# oresat0-plusz-end-card.net
KiCad netlist of a schematic drawn in EAGLE
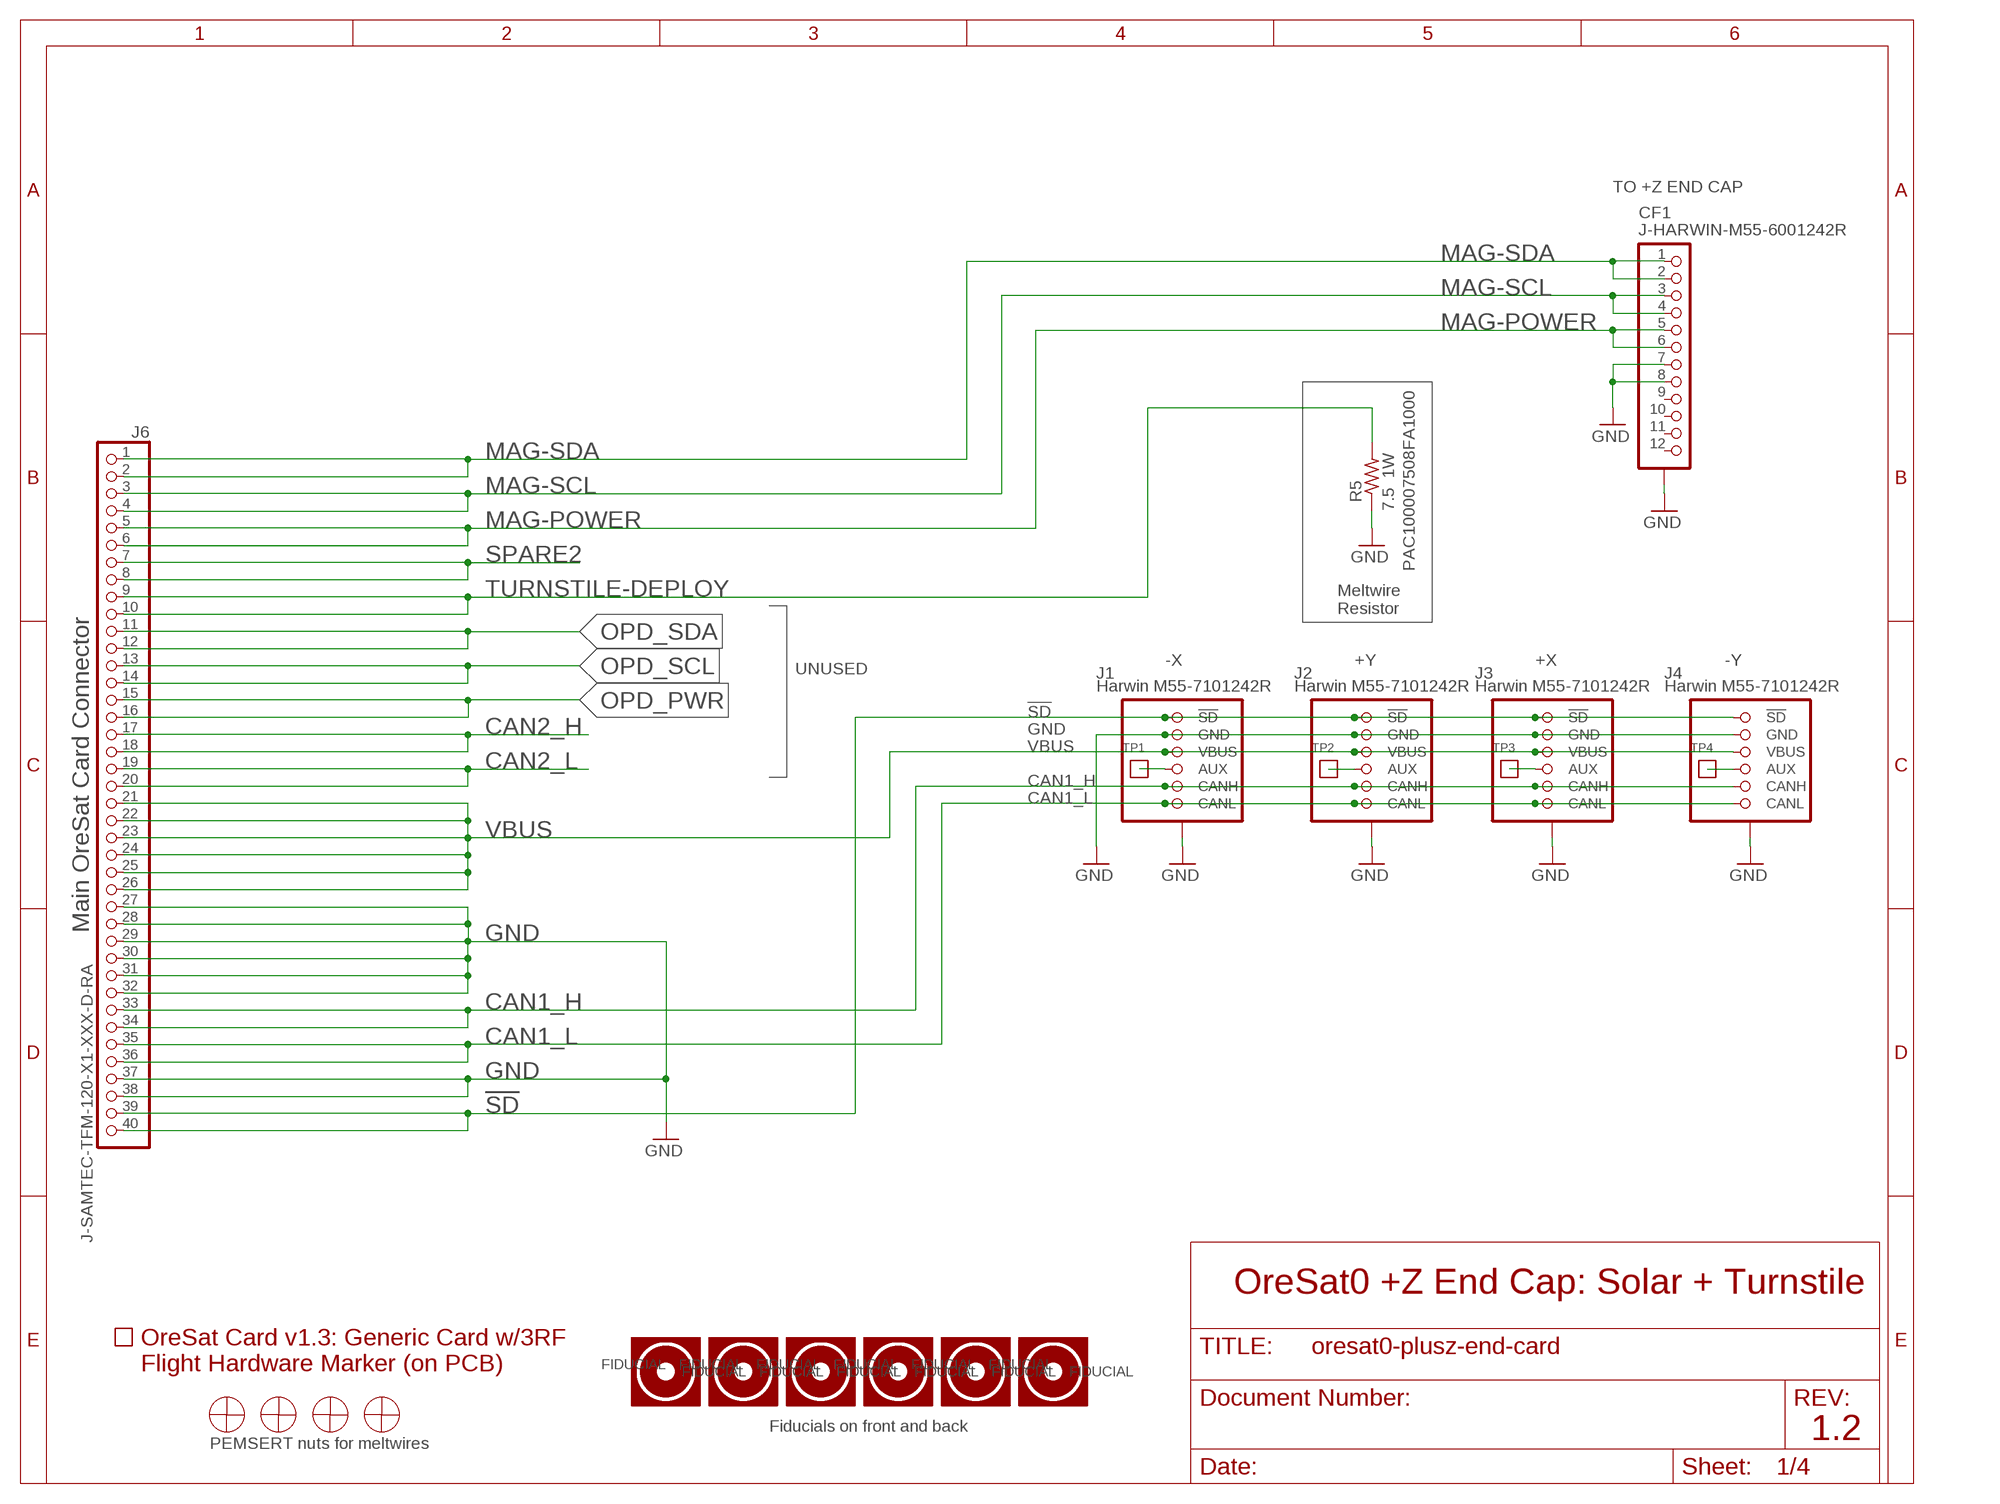
[diagram p0: schematic, sheet 1]
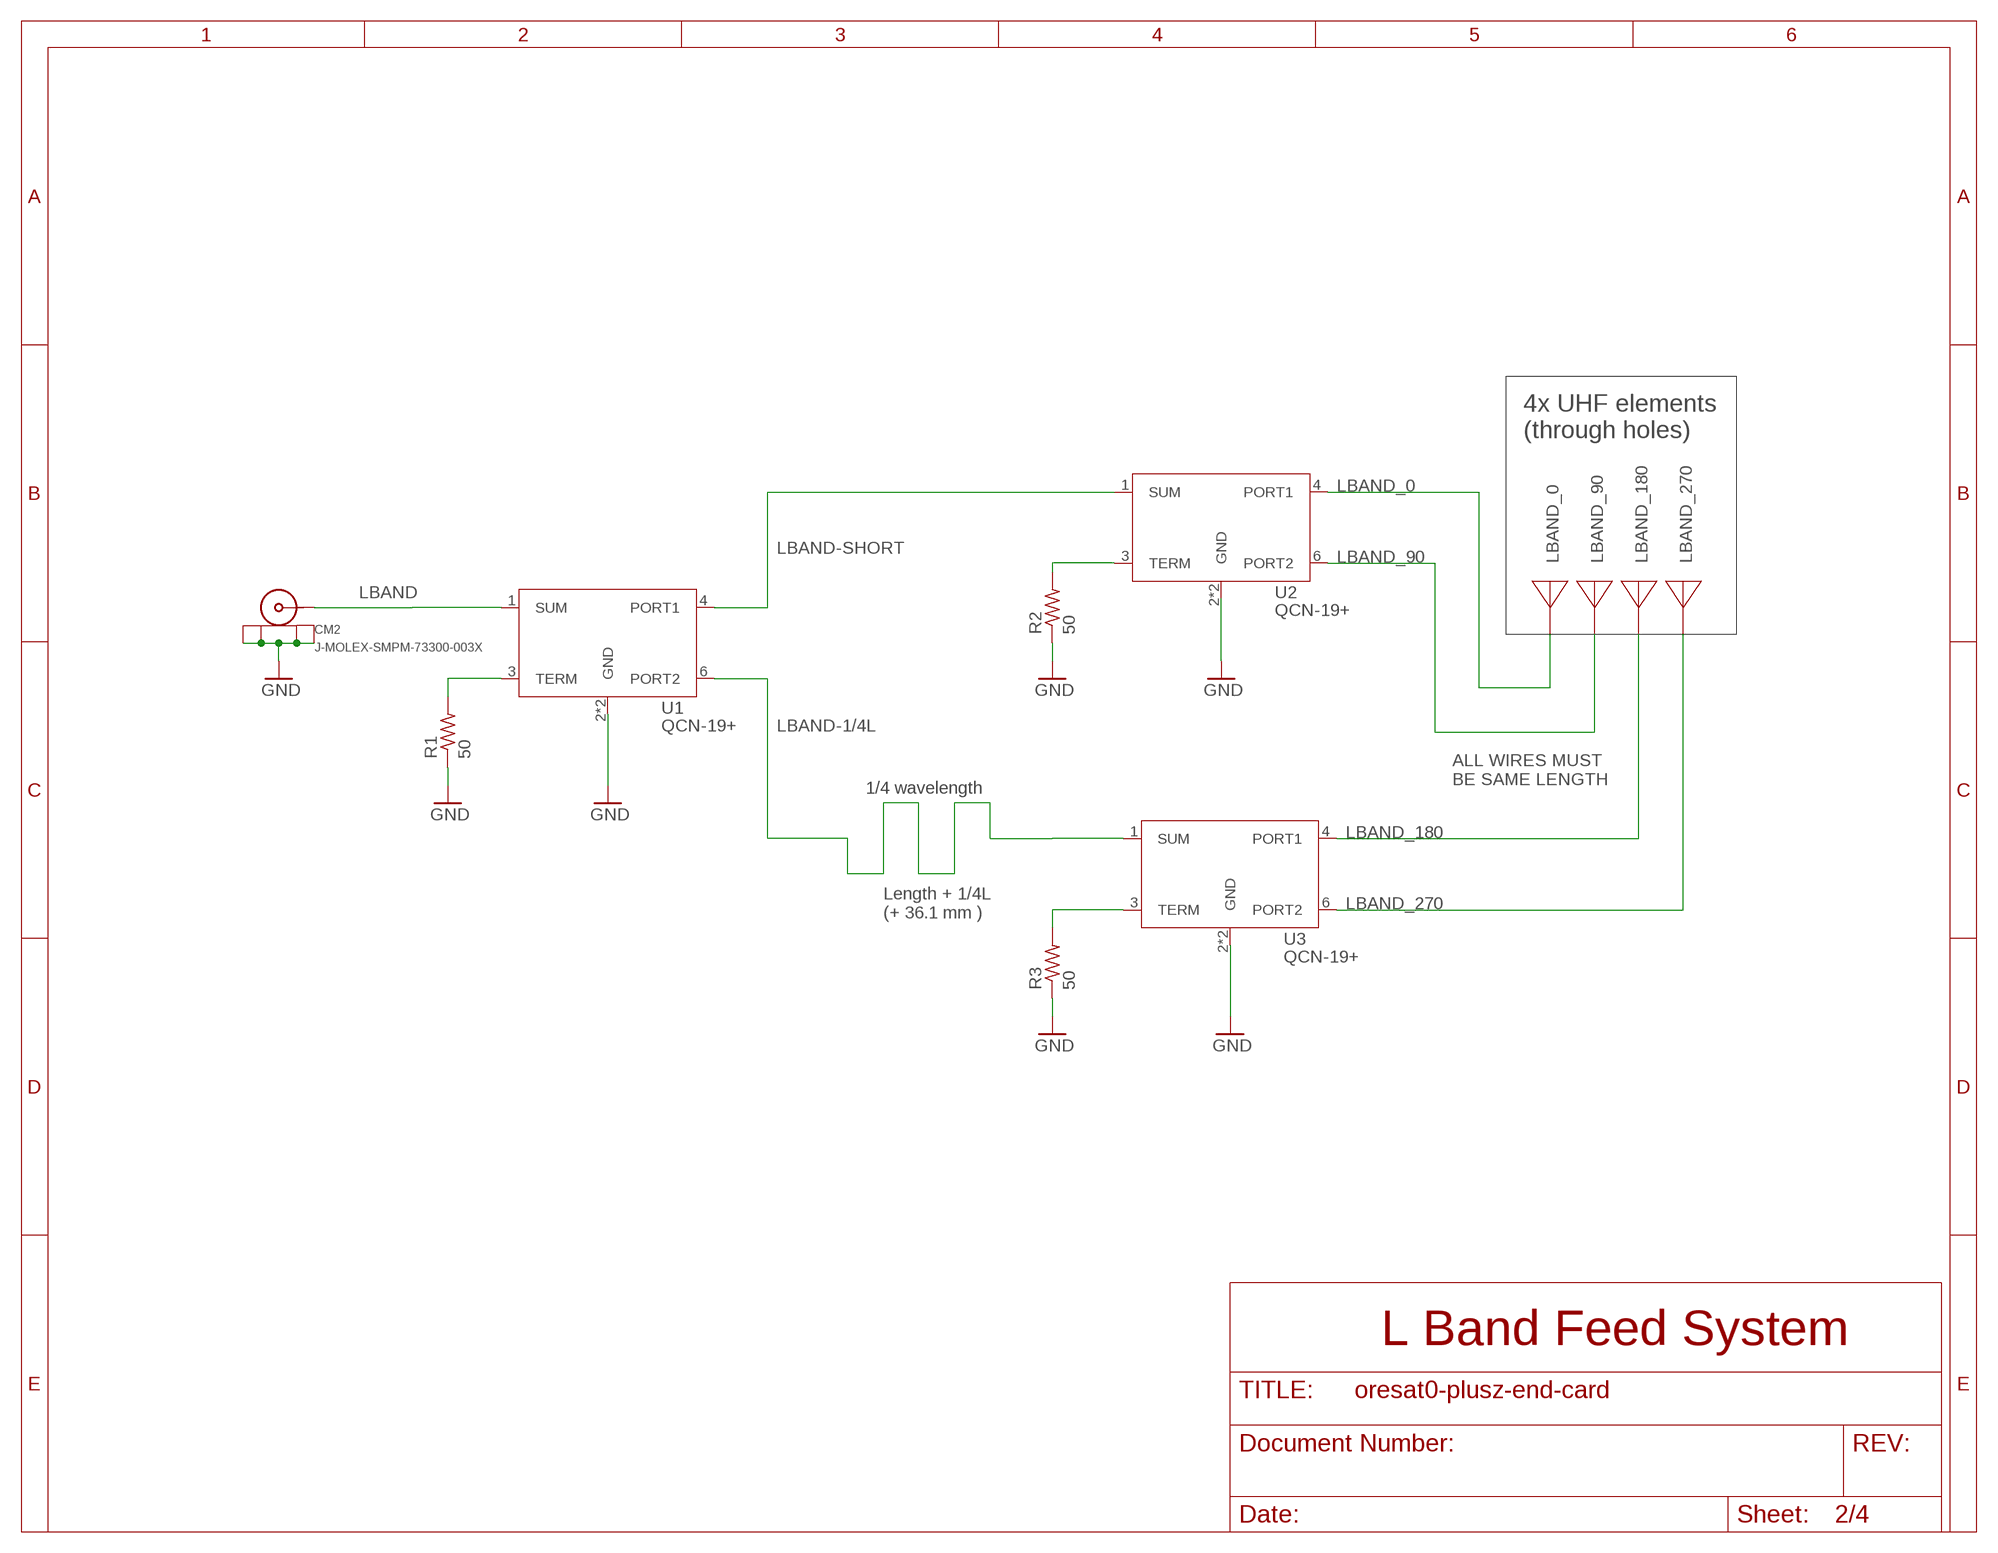
[diagram p1: schematic, sheet 2]
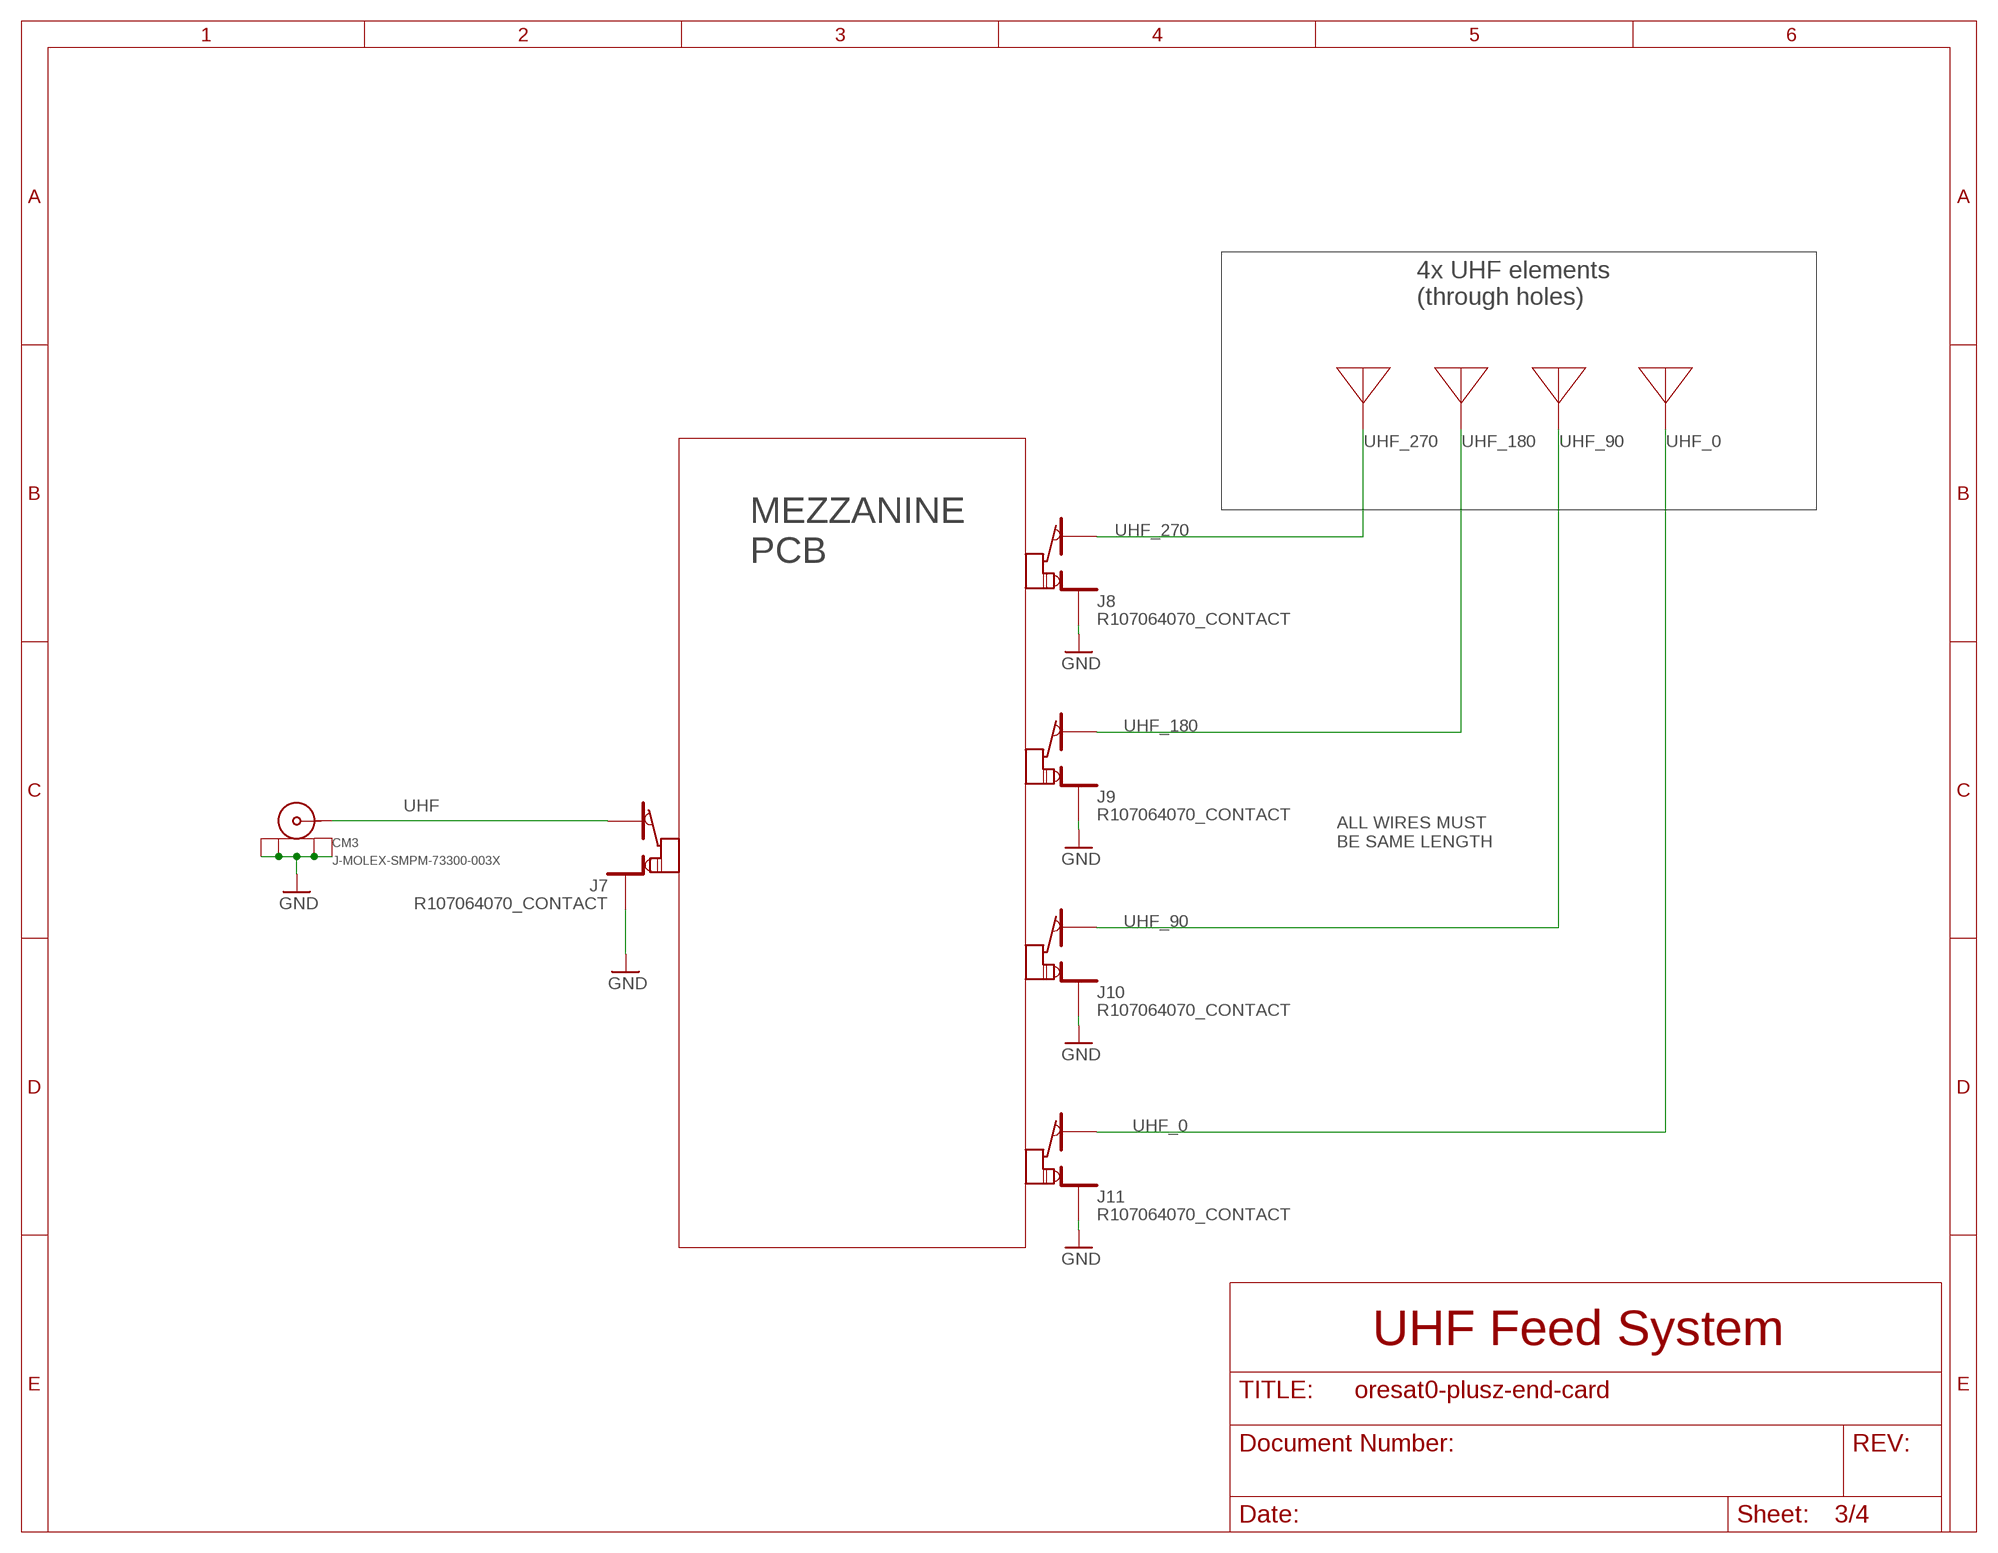
[diagram p2: schematic, sheet 3]
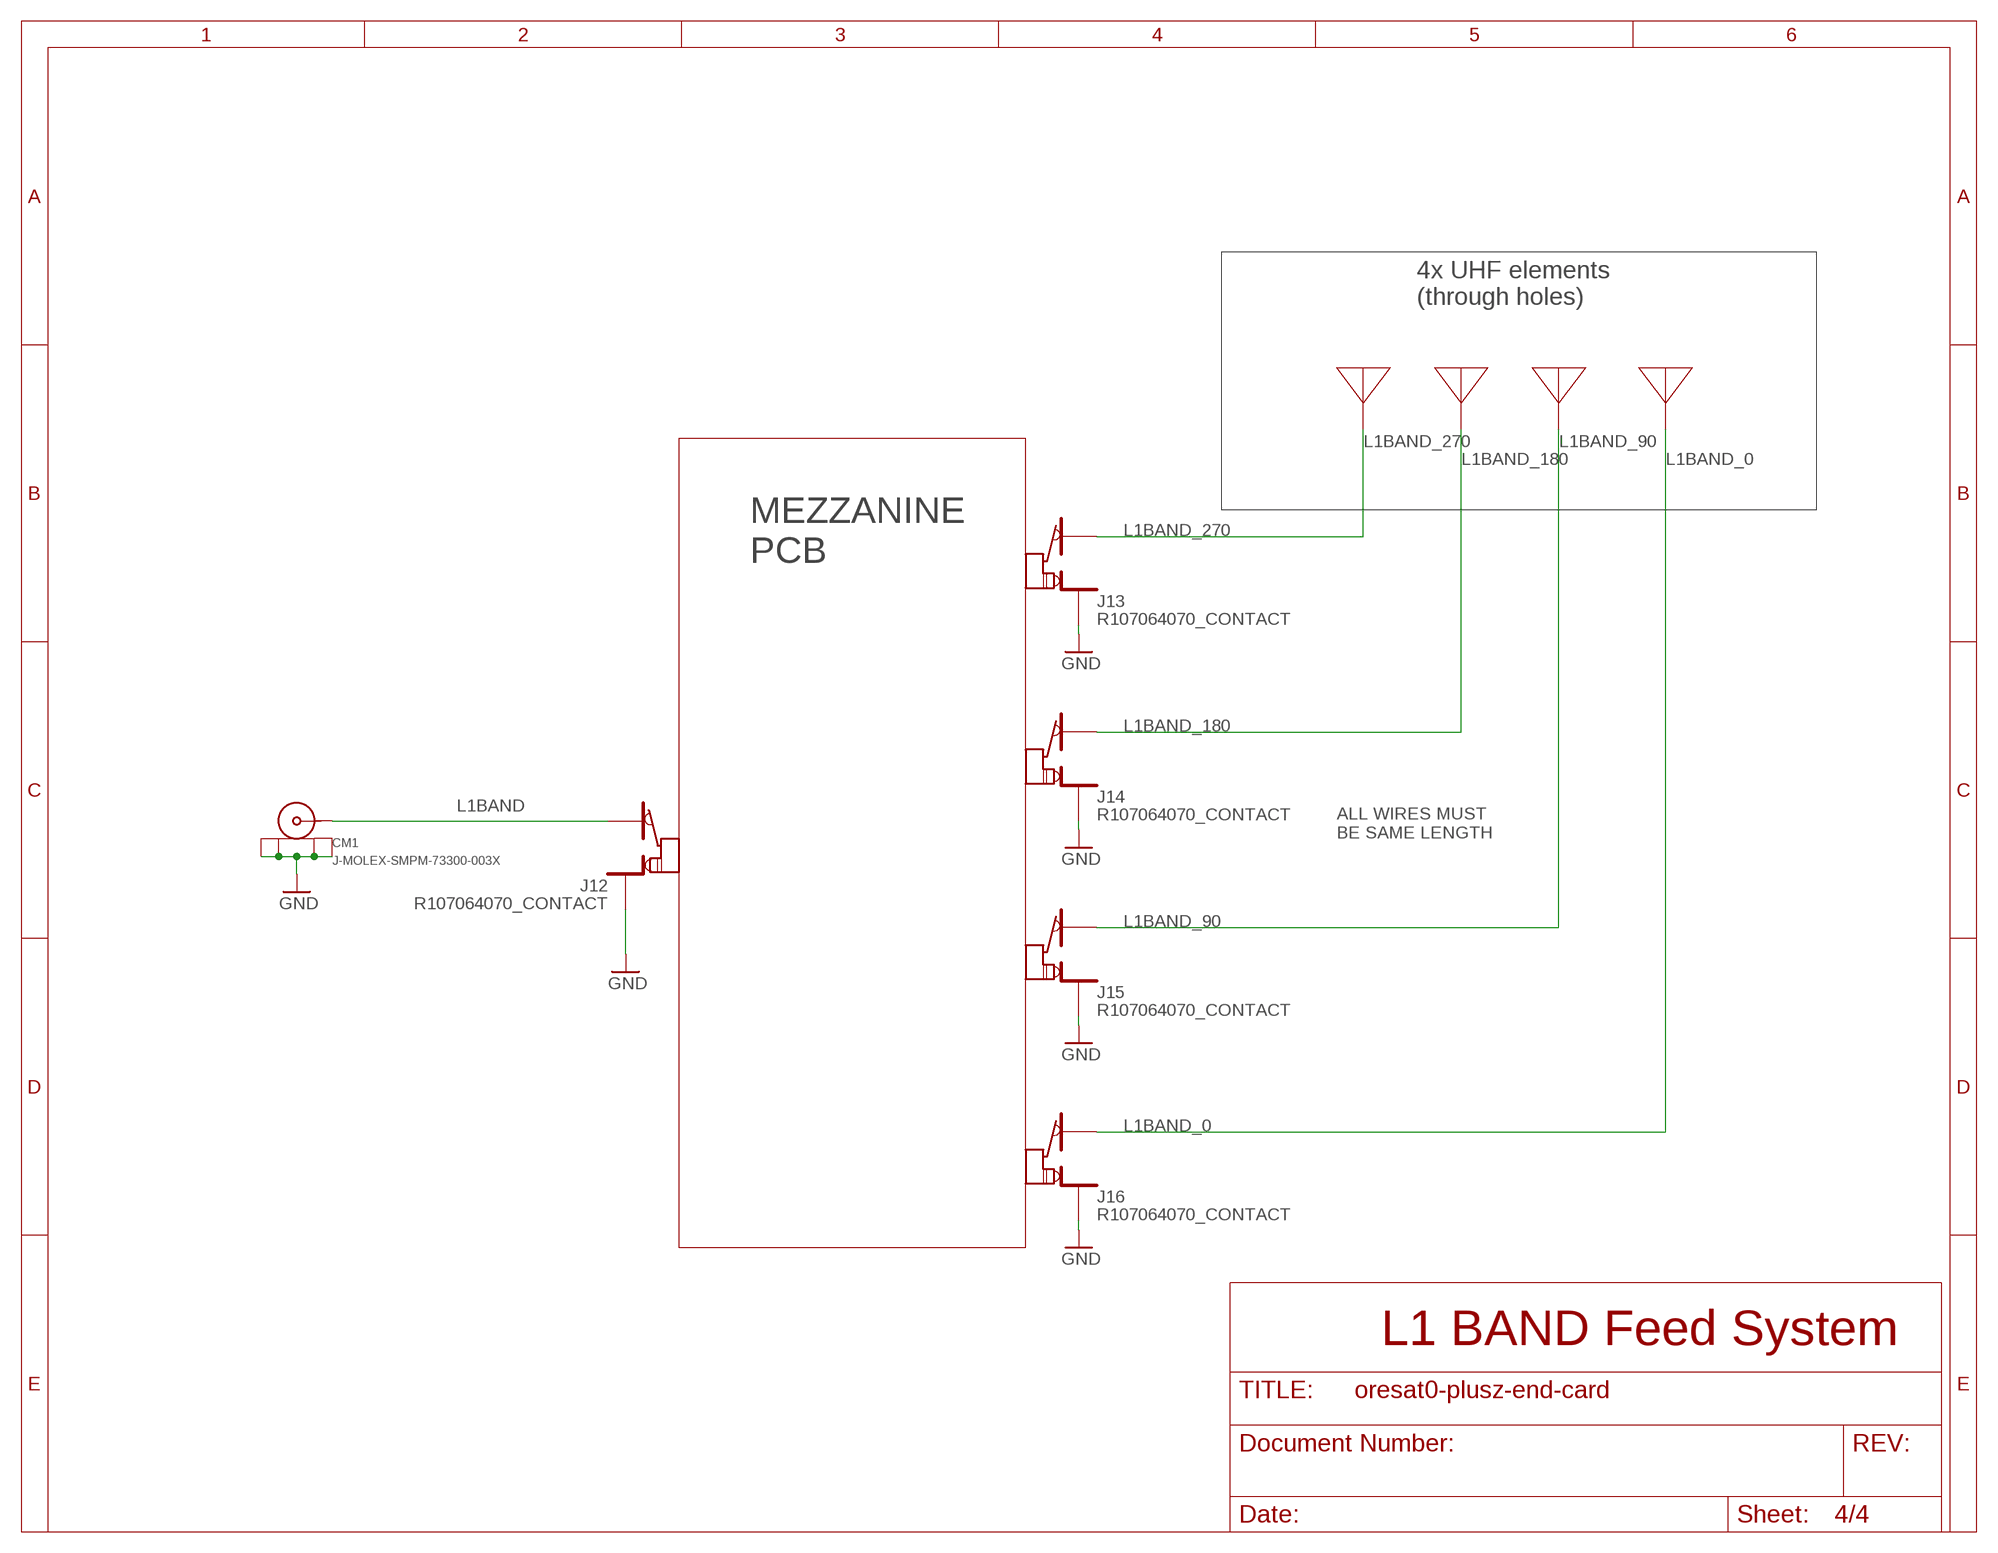
[diagram p3: schematic, sheet 4]

(export (version "E")
  (design (tool "Eeschema 10.0.6"))
  (components
    (comp (ref "CM2")
      (value "J-MOLEX-SMPM-73300-003X")
      (footprint "eagle-import:J-MOLEX-SMPM-073300-003X")
      (fields (field (name "MFG") "MOLEX"))
      (libsource (lib "eagle-import") (part "J-MOLEX-SMPM-73300-003X"))
    )
    (comp (ref "R1")
      (value "50")
      (footprint "eagle-import:.0603-C-NOSILK")
      (libsource (lib "eagle-import") (part "R-US_0603-C-NOSILK"))
    )
    (comp (ref "R2")
      (value "50")
      (footprint "eagle-import:.0603-C-NOSILK")
      (libsource (lib "eagle-import") (part "R-US_0603-C-NOSILK"))
    )
    (comp (ref "R3")
      (value "50")
      (footprint "eagle-import:.0603-C-NOSILK")
      (libsource (lib "eagle-import") (part "R-US_0603-C-NOSILK"))
    )
    (comp (ref "U1")
      (value "QCN-19+")
      (footprint "eagle-import:QCN-XXX+")
      (fields (field (name "MFG") "Mini-Circuits"))
      (libsource (lib "eagle-import") (part "QCN-XXX+"))
    )
    (comp (ref "U2")
      (value "QCN-19+")
      (footprint "eagle-import:QCN-XXX+")
      (fields (field (name "MFG") "Mini-Circuits"))
      (libsource (lib "eagle-import") (part "QCN-XXX+"))
    )
    (comp (ref "U3")
      (value "QCN-19+")
      (footprint "eagle-import:QCN-XXX+")
      (fields (field (name "MFG") "Mini-Circuits"))
      (libsource (lib "eagle-import") (part "QCN-XXX+"))
    )
    (comp (ref "CM3")
      (value "J-MOLEX-SMPM-73300-003X")
      (footprint "eagle-import:J-MOLEX-SMPM-073300-003X")
      (fields (field (name "MFG") "MOLEX"))
      (libsource (lib "eagle-import") (part "J-MOLEX-SMPM-73300-003X"))
    )
    (comp (ref "J7")
      (value "R107064070_CONTACT")
      (footprint "eagle-import:R107064070_CONTACT")
      (libsource (lib "eagle-import") (part "R107064070_CONTACT"))
    )
    (comp (ref "J8")
      (value "R107064070_CONTACT")
      (footprint "eagle-import:R107064070_CONTACT")
      (libsource (lib "eagle-import") (part "R107064070_CONTACT"))
    )
    (comp (ref "J9")
      (value "R107064070_CONTACT")
      (footprint "eagle-import:R107064070_CONTACT")
      (libsource (lib "eagle-import") (part "R107064070_CONTACT"))
    )
    (comp (ref "J10")
      (value "R107064070_CONTACT")
      (footprint "eagle-import:R107064070_CONTACT")
      (libsource (lib "eagle-import") (part "R107064070_CONTACT"))
    )
    (comp (ref "J11")
      (value "R107064070_CONTACT")
      (footprint "eagle-import:R107064070_CONTACT")
      (libsource (lib "eagle-import") (part "R107064070_CONTACT"))
    )
    (comp (ref "CM1")
      (value "J-MOLEX-SMPM-73300-003X")
      (footprint "eagle-import:J-MOLEX-SMPM-073300-003X")
      (fields (field (name "MFG") "MOLEX"))
      (libsource (lib "eagle-import") (part "J-MOLEX-SMPM-73300-003X"))
    )
    (comp (ref "J12")
      (value "R107064070_CONTACT")
      (footprint "eagle-import:R107064070_CONTACT")
      (libsource (lib "eagle-import") (part "R107064070_CONTACT"))
    )
    (comp (ref "J13")
      (value "R107064070_CONTACT")
      (footprint "eagle-import:R107064070_CONTACT")
      (libsource (lib "eagle-import") (part "R107064070_CONTACT"))
    )
    (comp (ref "J14")
      (value "R107064070_CONTACT")
      (footprint "eagle-import:R107064070_CONTACT")
      (libsource (lib "eagle-import") (part "R107064070_CONTACT"))
    )
    (comp (ref "J15")
      (value "R107064070_CONTACT")
      (footprint "eagle-import:R107064070_CONTACT")
      (libsource (lib "eagle-import") (part "R107064070_CONTACT"))
    )
    (comp (ref "J16")
      (value "R107064070_CONTACT")
      (footprint "eagle-import:R107064070_CONTACT")
      (libsource (lib "eagle-import") (part "R107064070_CONTACT"))
    )
    (comp (ref "CF1")
      (value "J-HARWIN-M55-6001242R")
      (footprint "eagle-import:HARWIN-M55-60X1242R")
      (fields (field (name "MFG") "Harwin"))
      (libsource (lib "eagle-import") (part "J-HARWIN-M55-60X1242R"))
    )
    (comp (ref "FIDUCIAL1")
      (value "FIDUCIAL-1.0X2.0")
      (footprint "eagle-import:FIDUCIAL-1.0X2.0")
      (libsource (lib "eagle-import") (part "FIDUCIAL-1.0X2.0"))
    )
    (comp (ref "FIDUCIAL2")
      (value "FIDUCIAL-1.0X2.0")
      (footprint "eagle-import:FIDUCIAL-1.0X2.0")
      (libsource (lib "eagle-import") (part "FIDUCIAL-1.0X2.0"))
    )
    (comp (ref "FIDUCIAL3")
      (value "FIDUCIAL-1.0X2.0")
      (footprint "eagle-import:FIDUCIAL-1.0X2.0")
      (libsource (lib "eagle-import") (part "FIDUCIAL-1.0X2.0"))
    )
    (comp (ref "FIDUCIAL4")
      (value "FIDUCIAL-1.0X2.0")
      (footprint "eagle-import:FIDUCIAL-1.0X2.0")
      (libsource (lib "eagle-import") (part "FIDUCIAL-1.0X2.0"))
    )
    (comp (ref "FIDUCIAL5")
      (value "FIDUCIAL-1.0X2.0")
      (footprint "eagle-import:FIDUCIAL-1.0X2.0")
      (libsource (lib "eagle-import") (part "FIDUCIAL-1.0X2.0"))
    )
    (comp (ref "FIDUCIAL6")
      (value "FIDUCIAL-1.0X2.0")
      (footprint "eagle-import:FIDUCIAL-1.0X2.0")
      (libsource (lib "eagle-import") (part "FIDUCIAL-1.0X2.0"))
    )
    (comp (ref "HW1")
      (value "MCMASTER-94100A150")
      (footprint "eagle-import:MCMASTER-94100A150")
      (libsource (lib "eagle-import") (part "MCMASTER-94100A150"))
    )
    (comp (ref "HW2")
      (value "MCMASTER-94100A150")
      (footprint "eagle-import:MCMASTER-94100A150")
      (libsource (lib "eagle-import") (part "MCMASTER-94100A150"))
    )
    (comp (ref "HW3")
      (value "MCMASTER-94100A150")
      (footprint "eagle-import:MCMASTER-94100A150")
      (libsource (lib "eagle-import") (part "MCMASTER-94100A150"))
    )
    (comp (ref "HW4")
      (value "MCMASTER-94100A150")
      (footprint "eagle-import:MCMASTER-94100A150")
      (libsource (lib "eagle-import") (part "MCMASTER-94100A150"))
    )
    (comp (ref "J1")
      (value "Harwin M55-7101242R")
      (footprint "eagle-import:M55-7101242R")
      (fields (field (name "MFG") "Harwin Inc."))
      (libsource (lib "eagle-import") (part "SOLAR-CARD-CONNECTOR"))
    )
    (comp (ref "J2")
      (value "Harwin M55-7101242R")
      (footprint "eagle-import:M55-7101242R")
      (fields (field (name "MFG") "Harwin Inc."))
      (libsource (lib "eagle-import") (part "SOLAR-CARD-CONNECTOR"))
    )
    (comp (ref "J3")
      (value "Harwin M55-7101242R")
      (footprint "eagle-import:M55-7101242R")
      (fields (field (name "MFG") "Harwin Inc."))
      (libsource (lib "eagle-import") (part "SOLAR-CARD-CONNECTOR"))
    )
    (comp (ref "J4")
      (value "Harwin M55-7101242R")
      (footprint "eagle-import:M55-7101242R")
      (fields (field (name "MFG") "Harwin Inc."))
      (libsource (lib "eagle-import") (part "SOLAR-CARD-CONNECTOR"))
    )
    (comp (ref "J6")
      (value "J-SAMTEC-TFM-120-X1-XXX-D-RA")
      (footprint "eagle-import:J-SAMTEC-TFM-120-X1-XXX-D-RA")
      (fields (field (name "MFR") "Samtec") (field (name "MPN") "TFM-120-01-L-D-RA"))
      (libsource (lib "eagle-import") (part "J-SAMTEC-TFM-120-X1-XXX-D-RA"))
    )
    (comp (ref "PCB1")
      (value "ORESAT-CARD-V1.3-GENERIC-3RF")
      (footprint "eagle-import:ORESAT-CARD-V1.3-GENERIC-3RF")
      (libsource (lib "eagle-import") (part "ORESAT-CARD-V1.3-GENERIC-3RF"))
    )
    (comp (ref "R5")
      (value "7.5 1W")
      (footprint "eagle-import:PAC100-FOR-MELTWIRE")
      (libsource (lib "eagle-import") (part "PAC100-FOR-MELTWIRE"))
    )
    (comp (ref "TP1")
      (value "TEST-POINT-LARGE-SQUARE")
      (footprint "eagle-import:1X01")
      (libsource (lib "eagle-import") (part "TEST-POINT-LARGE-SQUARE"))
    )
    (comp (ref "TP2")
      (value "TEST-POINT-LARGE-SQUARE")
      (footprint "eagle-import:1X01")
      (libsource (lib "eagle-import") (part "TEST-POINT-LARGE-SQUARE"))
    )
    (comp (ref "TP3")
      (value "TEST-POINT-LARGE-SQUARE")
      (footprint "eagle-import:1X01")
      (libsource (lib "eagle-import") (part "TEST-POINT-LARGE-SQUARE"))
    )
    (comp (ref "TP4")
      (value "TEST-POINT-LARGE-SQUARE")
      (footprint "eagle-import:1X01")
      (libsource (lib "eagle-import") (part "TEST-POINT-LARGE-SQUARE"))
    )
    (comp (ref "U$1")
      (value "FLIGHMARKERNEW")
      (footprint "eagle-import:FLIGHTMARKER_NEW_BOARDS")
      (libsource (lib "eagle-import") (part "FLIGHMARKERNEW"))
    )
  )
  (nets
    (net (code "1") (name "CAN1_H") (class "Default")
      (node (ref "J1") (pin "10") (pinfunction "CANH_10") (pintype "passive"))
      (node (ref "J1") (pin "9") (pinfunction "CANH_9") (pintype "passive"))
      (node (ref "J2") (pin "10") (pinfunction "CANH_10") (pintype "passive"))
      (node (ref "J2") (pin "9") (pinfunction "CANH_9") (pintype "passive"))
      (node (ref "J3") (pin "10") (pinfunction "CANH_10") (pintype "passive"))
      (node (ref "J3") (pin "9") (pinfunction "CANH_9") (pintype "passive"))
      (node (ref "J4") (pin "10") (pinfunction "CANH_10") (pintype "passive"))
      (node (ref "J4") (pin "9") (pinfunction "CANH_9") (pintype "passive"))
      (node (ref "J6") (pin "33") (pinfunction "33_33") (pintype "passive"))
      (node (ref "J6") (pin "34") (pinfunction "34_34") (pintype "passive"))
    )
    (net (code "2") (name "CAN1_L") (class "Default")
      (node (ref "J1") (pin "11") (pinfunction "CANL_11") (pintype "passive"))
      (node (ref "J1") (pin "12") (pinfunction "CANL_12") (pintype "passive"))
      (node (ref "J2") (pin "11") (pinfunction "CANL_11") (pintype "passive"))
      (node (ref "J2") (pin "12") (pinfunction "CANL_12") (pintype "passive"))
      (node (ref "J3") (pin "11") (pinfunction "CANL_11") (pintype "passive"))
      (node (ref "J3") (pin "12") (pinfunction "CANL_12") (pintype "passive"))
      (node (ref "J4") (pin "11") (pinfunction "CANL_11") (pintype "passive"))
      (node (ref "J4") (pin "12") (pinfunction "CANL_12") (pintype "passive"))
      (node (ref "J6") (pin "35") (pinfunction "35_35") (pintype "passive"))
      (node (ref "J6") (pin "36") (pinfunction "36_36") (pintype "passive"))
    )
    (net (code "3") (name "CAN2_H") (class "Default")
      (node (ref "J6") (pin "17") (pinfunction "17_17") (pintype "passive"))
      (node (ref "J6") (pin "18") (pinfunction "18_18") (pintype "passive"))
    )
    (net (code "4") (name "CAN2_L") (class "Default")
      (node (ref "J6") (pin "19") (pinfunction "19_19") (pintype "passive"))
      (node (ref "J6") (pin "20") (pinfunction "20_20") (pintype "passive"))
    )
    (net (code "5") (name "GND") (class "Default")
      (node (ref "CF1") (pin "7") (pinfunction "7_7") (pintype "passive"))
      (node (ref "CF1") (pin "8") (pinfunction "8_8") (pintype "passive"))
      (node (ref "CF1") (pin "P$1") (pinfunction "SHIELDS_P$1") (pintype "passive"))
      (node (ref "CF1") (pin "P$2") (pinfunction "SHIELDS_P$2") (pintype "passive"))
      (node (ref "CF1") (pin "P$3") (pinfunction "SHIELDS_P$3") (pintype "passive"))
      (node (ref "CF1") (pin "P$4") (pinfunction "SHIELDS_P$4") (pintype "passive"))
      (node (ref "CM1") (pin "P$1") (pinfunction "SHIELD3_P$1") (pintype "passive"))
      (node (ref "CM1") (pin "P$2") (pinfunction "SHIELD2_P$2") (pintype "passive"))
      (node (ref "CM1") (pin "P$3") (pinfunction "SHIELD1_P$3") (pintype "passive"))
      (node (ref "CM1") (pin "P$4") (pinfunction "SHIELD_P$4") (pintype "passive"))
      (node (ref "CM2") (pin "P$1") (pinfunction "SHIELD3_P$1") (pintype "passive"))
      (node (ref "CM2") (pin "P$2") (pinfunction "SHIELD2_P$2") (pintype "passive"))
      (node (ref "CM2") (pin "P$3") (pinfunction "SHIELD1_P$3") (pintype "passive"))
      (node (ref "CM2") (pin "P$4") (pinfunction "SHIELD_P$4") (pintype "passive"))
      (node (ref "CM3") (pin "P$1") (pinfunction "SHIELD3_P$1") (pintype "passive"))
      (node (ref "CM3") (pin "P$2") (pinfunction "SHIELD2_P$2") (pintype "passive"))
      (node (ref "CM3") (pin "P$3") (pinfunction "SHIELD1_P$3") (pintype "passive"))
      (node (ref "CM3") (pin "P$4") (pinfunction "SHIELD_P$4") (pintype "passive"))
      (node (ref "J1") (pin "3") (pinfunction "GND_3") (pintype "passive"))
      (node (ref "J1") (pin "4") (pinfunction "GND_4") (pintype "passive"))
      (node (ref "J1") (pin "P$1") (pinfunction "SHIELD_P$1") (pintype "passive"))
      (node (ref "J1") (pin "P$2") (pinfunction "SHIELD_P$2") (pintype "passive"))
      (node (ref "J1") (pin "P$3") (pinfunction "SHIELD_P$3") (pintype "passive"))
      (node (ref "J1") (pin "P$4") (pinfunction "SHIELD_P$4") (pintype "passive"))
      (node (ref "J10") (pin "P$2") (pinfunction "P$2_P$2") (pintype "bidirectional"))
      (node (ref "J10") (pin "P$3") (pinfunction "P$2_P$3") (pintype "bidirectional"))
      (node (ref "J11") (pin "P$2") (pinfunction "P$2_P$2") (pintype "bidirectional"))
      (node (ref "J11") (pin "P$3") (pinfunction "P$2_P$3") (pintype "bidirectional"))
      (node (ref "J12") (pin "P$2") (pinfunction "P$2_P$2") (pintype "bidirectional"))
      (node (ref "J12") (pin "P$3") (pinfunction "P$2_P$3") (pintype "bidirectional"))
      (node (ref "J13") (pin "P$2") (pinfunction "P$2_P$2") (pintype "bidirectional"))
      (node (ref "J13") (pin "P$3") (pinfunction "P$2_P$3") (pintype "bidirectional"))
      (node (ref "J14") (pin "P$2") (pinfunction "P$2_P$2") (pintype "bidirectional"))
      (node (ref "J14") (pin "P$3") (pinfunction "P$2_P$3") (pintype "bidirectional"))
      (node (ref "J15") (pin "P$2") (pinfunction "P$2_P$2") (pintype "bidirectional"))
      (node (ref "J15") (pin "P$3") (pinfunction "P$2_P$3") (pintype "bidirectional"))
      (node (ref "J16") (pin "P$2") (pinfunction "P$2_P$2") (pintype "bidirectional"))
      (node (ref "J16") (pin "P$3") (pinfunction "P$2_P$3") (pintype "bidirectional"))
      (node (ref "J2") (pin "3") (pinfunction "GND_3") (pintype "passive"))
      (node (ref "J2") (pin "4") (pinfunction "GND_4") (pintype "passive"))
      (node (ref "J2") (pin "P$1") (pinfunction "SHIELD_P$1") (pintype "passive"))
      (node (ref "J2") (pin "P$2") (pinfunction "SHIELD_P$2") (pintype "passive"))
      (node (ref "J2") (pin "P$3") (pinfunction "SHIELD_P$3") (pintype "passive"))
      (node (ref "J2") (pin "P$4") (pinfunction "SHIELD_P$4") (pintype "passive"))
      (node (ref "J3") (pin "3") (pinfunction "GND_3") (pintype "passive"))
      (node (ref "J3") (pin "4") (pinfunction "GND_4") (pintype "passive"))
      (node (ref "J3") (pin "P$1") (pinfunction "SHIELD_P$1") (pintype "passive"))
      (node (ref "J3") (pin "P$2") (pinfunction "SHIELD_P$2") (pintype "passive"))
      (node (ref "J3") (pin "P$3") (pinfunction "SHIELD_P$3") (pintype "passive"))
      (node (ref "J3") (pin "P$4") (pinfunction "SHIELD_P$4") (pintype "passive"))
      (node (ref "J4") (pin "3") (pinfunction "GND_3") (pintype "passive"))
      (node (ref "J4") (pin "4") (pinfunction "GND_4") (pintype "passive"))
      (node (ref "J4") (pin "P$1") (pinfunction "SHIELD_P$1") (pintype "passive"))
      (node (ref "J4") (pin "P$2") (pinfunction "SHIELD_P$2") (pintype "passive"))
      (node (ref "J4") (pin "P$3") (pinfunction "SHIELD_P$3") (pintype "passive"))
      (node (ref "J4") (pin "P$4") (pinfunction "SHIELD_P$4") (pintype "passive"))
      (node (ref "J6") (pin "27") (pinfunction "27_27") (pintype "passive"))
      (node (ref "J6") (pin "28") (pinfunction "28_28") (pintype "passive"))
      (node (ref "J6") (pin "29") (pinfunction "29_29") (pintype "passive"))
      (node (ref "J6") (pin "30") (pinfunction "30_30") (pintype "passive"))
      (node (ref "J6") (pin "31") (pinfunction "31_31") (pintype "passive"))
      (node (ref "J6") (pin "32") (pinfunction "32_32") (pintype "passive"))
      (node (ref "J6") (pin "37") (pinfunction "37_37") (pintype "passive"))
      (node (ref "J6") (pin "38") (pinfunction "38_38") (pintype "passive"))
      (node (ref "J7") (pin "P$2") (pinfunction "P$2_P$2") (pintype "bidirectional"))
      (node (ref "J7") (pin "P$3") (pinfunction "P$2_P$3") (pintype "bidirectional"))
      (node (ref "J8") (pin "P$2") (pinfunction "P$2_P$2") (pintype "bidirectional"))
      (node (ref "J8") (pin "P$3") (pinfunction "P$2_P$3") (pintype "bidirectional"))
      (node (ref "J9") (pin "P$2") (pinfunction "P$2_P$2") (pintype "bidirectional"))
      (node (ref "J9") (pin "P$3") (pinfunction "P$2_P$3") (pintype "bidirectional"))
      (node (ref "R1") (pin "1") (pinfunction "1_1") (pintype "passive"))
      (node (ref "R2") (pin "1") (pinfunction "1_1") (pintype "passive"))
      (node (ref "R3") (pin "1") (pinfunction "1_1") (pintype "passive"))
      (node (ref "R5") (pin "P$1") (pinfunction "1_P$1") (pintype "passive"))
      (node (ref "R5") (pin "P$2") (pinfunction "1_P$2") (pintype "passive"))
      (node (ref "U1") (pin "2") (pinfunction "GND_2") (pintype "power_in"))
      (node (ref "U1") (pin "5") (pinfunction "GND_5") (pintype "power_in"))
      (node (ref "U2") (pin "2") (pinfunction "GND_2") (pintype "power_in"))
      (node (ref "U2") (pin "5") (pinfunction "GND_5") (pintype "power_in"))
      (node (ref "U3") (pin "2") (pinfunction "GND_2") (pintype "power_in"))
      (node (ref "U3") (pin "5") (pinfunction "GND_5") (pintype "power_in"))
    )
    (net (code "6") (name "L1BAND") (class "Default")
      (node (ref "CM1") (pin "RF") (pinfunction "CENTER_RF") (pintype "passive"))
      (node (ref "J12") (pin "P$1") (pinfunction "P$1_P$1") (pintype "bidirectional"))
    )
    (net (code "7") (name "L1BAND_0") (class "Default")
      (node (ref "J16") (pin "P$1") (pinfunction "P$1_P$1") (pintype "bidirectional"))
    )
    (net (code "8") (name "L1BAND_90") (class "Default")
      (node (ref "J15") (pin "P$1") (pinfunction "P$1_P$1") (pintype "bidirectional"))
    )
    (net (code "9") (name "L1BAND_180") (class "Default")
      (node (ref "J14") (pin "P$1") (pinfunction "P$1_P$1") (pintype "bidirectional"))
    )
    (net (code "10") (name "L1BAND_270") (class "Default")
      (node (ref "J13") (pin "P$1") (pinfunction "P$1_P$1") (pintype "bidirectional"))
    )
    (net (code "11") (name "LBAND") (class "Default")
      (node (ref "CM2") (pin "RF") (pinfunction "CENTER_RF") (pintype "passive"))
      (node (ref "U1") (pin "1") (pinfunction "SUM_1") (pintype "bidirectional"))
    )
    (net (code "12") (name "LBAND-1{slash}4L") (class "Default")
      (node (ref "U1") (pin "6") (pinfunction "PORT2_6") (pintype "bidirectional"))
      (node (ref "U3") (pin "1") (pinfunction "SUM_1") (pintype "bidirectional"))
    )
    (net (code "13") (name "LBAND-SHORT") (class "Default")
      (node (ref "U1") (pin "4") (pinfunction "PORT1_4") (pintype "bidirectional"))
      (node (ref "U2") (pin "1") (pinfunction "SUM_1") (pintype "bidirectional"))
    )
    (net (code "14") (name "LBAND_0") (class "Default")
      (node (ref "U2") (pin "4") (pinfunction "PORT1_4") (pintype "bidirectional"))
    )
    (net (code "15") (name "LBAND_90") (class "Default")
      (node (ref "U2") (pin "6") (pinfunction "PORT2_6") (pintype "bidirectional"))
    )
    (net (code "16") (name "LBAND_180") (class "Default")
      (node (ref "U3") (pin "4") (pinfunction "PORT1_4") (pintype "bidirectional"))
    )
    (net (code "17") (name "LBAND_270") (class "Default")
      (node (ref "U3") (pin "6") (pinfunction "PORT2_6") (pintype "bidirectional"))
    )
    (net (code "18") (name "MAG-POWER") (class "Default")
      (node (ref "CF1") (pin "5") (pinfunction "5_5") (pintype "passive"))
      (node (ref "CF1") (pin "6") (pinfunction "6_6") (pintype "passive"))
      (node (ref "J6") (pin "5") (pinfunction "5_5") (pintype "passive"))
      (node (ref "J6") (pin "6") (pinfunction "6_6") (pintype "passive"))
    )
    (net (code "19") (name "MAG-SCL") (class "Default")
      (node (ref "CF1") (pin "3") (pinfunction "3_3") (pintype "passive"))
      (node (ref "CF1") (pin "4") (pinfunction "4_4") (pintype "passive"))
      (node (ref "J6") (pin "3") (pinfunction "3_3") (pintype "passive"))
      (node (ref "J6") (pin "4") (pinfunction "4_4") (pintype "passive"))
    )
    (net (code "20") (name "MAG-SDA") (class "Default")
      (node (ref "CF1") (pin "1") (pinfunction "1_1") (pintype "passive"))
      (node (ref "CF1") (pin "2") (pinfunction "2_2") (pintype "passive"))
      (node (ref "J6") (pin "1") (pinfunction "1_1") (pintype "passive"))
      (node (ref "J6") (pin "2") (pinfunction "2_2") (pintype "passive"))
    )
    (net (code "21") (name "Net-(J1-AUX-Pad7)") (class "Default")
      (node (ref "J1") (pin "7") (pinfunction "AUX_7") (pintype "passive"))
      (node (ref "J1") (pin "8") (pinfunction "AUX_8") (pintype "passive"))
      (node (ref "TP1") (pin "1") (pinfunction "1_1") (pintype "passive"))
    )
    (net (code "22") (name "Net-(J2-AUX-Pad7)") (class "Default")
      (node (ref "J2") (pin "7") (pinfunction "AUX_7") (pintype "passive"))
      (node (ref "J2") (pin "8") (pinfunction "AUX_8") (pintype "passive"))
      (node (ref "TP2") (pin "1") (pinfunction "1_1") (pintype "passive"))
    )
    (net (code "23") (name "Net-(J3-AUX-Pad7)") (class "Default")
      (node (ref "J3") (pin "7") (pinfunction "AUX_7") (pintype "passive"))
      (node (ref "J3") (pin "8") (pinfunction "AUX_8") (pintype "passive"))
      (node (ref "TP3") (pin "1") (pinfunction "1_1") (pintype "passive"))
    )
    (net (code "24") (name "Net-(J4-AUX-Pad7)") (class "Default")
      (node (ref "J4") (pin "7") (pinfunction "AUX_7") (pintype "passive"))
      (node (ref "J4") (pin "8") (pinfunction "AUX_8") (pintype "passive"))
      (node (ref "TP4") (pin "1") (pinfunction "1_1") (pintype "passive"))
    )
    (net (code "25") (name "Net-(U1-TERM)") (class "Default")
      (node (ref "R1") (pin "2") (pinfunction "2_2") (pintype "passive"))
      (node (ref "U1") (pin "3") (pinfunction "TERM_3") (pintype "bidirectional"))
    )
    (net (code "26") (name "Net-(U2-TERM)") (class "Default")
      (node (ref "R2") (pin "2") (pinfunction "2_2") (pintype "passive"))
      (node (ref "U2") (pin "3") (pinfunction "TERM_3") (pintype "bidirectional"))
    )
    (net (code "27") (name "Net-(U3-TERM)") (class "Default")
      (node (ref "R3") (pin "2") (pinfunction "2_2") (pintype "passive"))
      (node (ref "U3") (pin "3") (pinfunction "TERM_3") (pintype "bidirectional"))
    )
    (net (code "28") (name "OPD_PWR") (class "Default")
      (node (ref "J6") (pin "15") (pinfunction "15_15") (pintype "passive"))
      (node (ref "J6") (pin "16") (pinfunction "16_16") (pintype "passive"))
    )
    (net (code "29") (name "OPD_SCL") (class "Default")
      (node (ref "J6") (pin "13") (pinfunction "13_13") (pintype "passive"))
      (node (ref "J6") (pin "14") (pinfunction "14_14") (pintype "passive"))
    )
    (net (code "30") (name "OPD_SDA") (class "Default")
      (node (ref "J6") (pin "11") (pinfunction "11_11") (pintype "passive"))
      (node (ref "J6") (pin "12") (pinfunction "12_12") (pintype "passive"))
    )
    (net (code "31") (name "SPARE2") (class "Default")
      (node (ref "J6") (pin "7") (pinfunction "7_7") (pintype "passive"))
      (node (ref "J6") (pin "8") (pinfunction "8_8") (pintype "passive"))
    )
    (net (code "32") (name "TURNSTILE-DEPLOY") (class "Default")
      (node (ref "J6") (pin "10") (pinfunction "10_10") (pintype "passive"))
      (node (ref "J6") (pin "9") (pinfunction "9_9") (pintype "passive"))
      (node (ref "R5") (pin "P$3") (pinfunction "2_P$3") (pintype "passive"))
      (node (ref "R5") (pin "P$4") (pinfunction "2_P$4") (pintype "passive"))
    )
    (net (code "33") (name "UHF") (class "Default")
      (node (ref "CM3") (pin "RF") (pinfunction "CENTER_RF") (pintype "passive"))
      (node (ref "J7") (pin "P$1") (pinfunction "P$1_P$1") (pintype "bidirectional"))
    )
    (net (code "34") (name "UHF_0") (class "Default")
      (node (ref "J11") (pin "P$1") (pinfunction "P$1_P$1") (pintype "bidirectional"))
    )
    (net (code "35") (name "UHF_90") (class "Default")
      (node (ref "J10") (pin "P$1") (pinfunction "P$1_P$1") (pintype "bidirectional"))
    )
    (net (code "36") (name "UHF_180") (class "Default")
      (node (ref "J9") (pin "P$1") (pinfunction "P$1_P$1") (pintype "bidirectional"))
    )
    (net (code "37") (name "UHF_270") (class "Default")
      (node (ref "J8") (pin "P$1") (pinfunction "P$1_P$1") (pintype "bidirectional"))
    )
    (net (code "38") (name "VBUS") (class "Default")
      (node (ref "J1") (pin "5") (pinfunction "VBUS_5") (pintype "passive"))
      (node (ref "J1") (pin "6") (pinfunction "VBUS_6") (pintype "passive"))
      (node (ref "J2") (pin "5") (pinfunction "VBUS_5") (pintype "passive"))
      (node (ref "J2") (pin "6") (pinfunction "VBUS_6") (pintype "passive"))
      (node (ref "J3") (pin "5") (pinfunction "VBUS_5") (pintype "passive"))
      (node (ref "J3") (pin "6") (pinfunction "VBUS_6") (pintype "passive"))
      (node (ref "J4") (pin "5") (pinfunction "VBUS_5") (pintype "passive"))
      (node (ref "J4") (pin "6") (pinfunction "VBUS_6") (pintype "passive"))
      (node (ref "J6") (pin "21") (pinfunction "21_21") (pintype "passive"))
      (node (ref "J6") (pin "22") (pinfunction "22_22") (pintype "passive"))
      (node (ref "J6") (pin "23") (pinfunction "23_23") (pintype "passive"))
      (node (ref "J6") (pin "24") (pinfunction "24_24") (pintype "passive"))
      (node (ref "J6") (pin "25") (pinfunction "25_25") (pintype "passive"))
      (node (ref "J6") (pin "26") (pinfunction "26_26") (pintype "passive"))
    )
    (net (code "39") (name "unconnected-(CF1-Pad9)") (class "Default")
      (node (ref "CF1") (pin "9") (pinfunction "9_9") (pintype "passive"))
    )
    (net (code "40") (name "unconnected-(CF1-Pad10)") (class "Default")
      (node (ref "CF1") (pin "10") (pinfunction "10_10") (pintype "passive"))
    )
    (net (code "41") (name "unconnected-(CF1-Pad11)") (class "Default")
      (node (ref "CF1") (pin "11") (pinfunction "11_11") (pintype "passive"))
    )
    (net (code "42") (name "unconnected-(CF1-Pad12)") (class "Default")
      (node (ref "CF1") (pin "12") (pinfunction "12_12") (pintype "passive"))
    )
    (net (code "43") (name "unconnected-(FIDUCIAL1-PadFIDUCIAL)") (class "Default")
      (node (ref "FIDUCIAL1") (pin "FIDUCIAL") (pinfunction "FIDUCIAL_FIDUCIAL") (pintype "no_connect"))
    )
    (net (code "44") (name "unconnected-(FIDUCIAL2-PadFIDUCIAL)") (class "Default")
      (node (ref "FIDUCIAL2") (pin "FIDUCIAL") (pinfunction "FIDUCIAL_FIDUCIAL") (pintype "no_connect"))
    )
    (net (code "45") (name "unconnected-(FIDUCIAL3-PadFIDUCIAL)") (class "Default")
      (node (ref "FIDUCIAL3") (pin "FIDUCIAL") (pinfunction "FIDUCIAL_FIDUCIAL") (pintype "no_connect"))
    )
    (net (code "46") (name "unconnected-(FIDUCIAL4-PadFIDUCIAL)") (class "Default")
      (node (ref "FIDUCIAL4") (pin "FIDUCIAL") (pinfunction "FIDUCIAL_FIDUCIAL") (pintype "no_connect"))
    )
    (net (code "47") (name "unconnected-(FIDUCIAL5-PadFIDUCIAL)") (class "Default")
      (node (ref "FIDUCIAL5") (pin "FIDUCIAL") (pinfunction "FIDUCIAL_FIDUCIAL") (pintype "no_connect"))
    )
    (net (code "48") (name "unconnected-(FIDUCIAL6-PadFIDUCIAL)") (class "Default")
      (node (ref "FIDUCIAL6") (pin "FIDUCIAL") (pinfunction "FIDUCIAL_FIDUCIAL") (pintype "no_connect"))
    )
    (net (code "49") (name "~{SD}") (class "Default")
      (node (ref "J1") (pin "1") (pinfunction "~{SD}_1") (pintype "passive"))
      (node (ref "J1") (pin "2") (pinfunction "~{SD}_2") (pintype "passive"))
      (node (ref "J2") (pin "1") (pinfunction "~{SD}_1") (pintype "passive"))
      (node (ref "J2") (pin "2") (pinfunction "~{SD}_2") (pintype "passive"))
      (node (ref "J3") (pin "1") (pinfunction "~{SD}_1") (pintype "passive"))
      (node (ref "J3") (pin "2") (pinfunction "~{SD}_2") (pintype "passive"))
      (node (ref "J4") (pin "1") (pinfunction "~{SD}_1") (pintype "passive"))
      (node (ref "J4") (pin "2") (pinfunction "~{SD}_2") (pintype "passive"))
      (node (ref "J6") (pin "39") (pinfunction "39_39") (pintype "passive"))
      (node (ref "J6") (pin "40") (pinfunction "40_40") (pintype "passive"))
    )
  )
)
